# imu_node.net
KiCad netlist of a schematic drawn in EAGLE
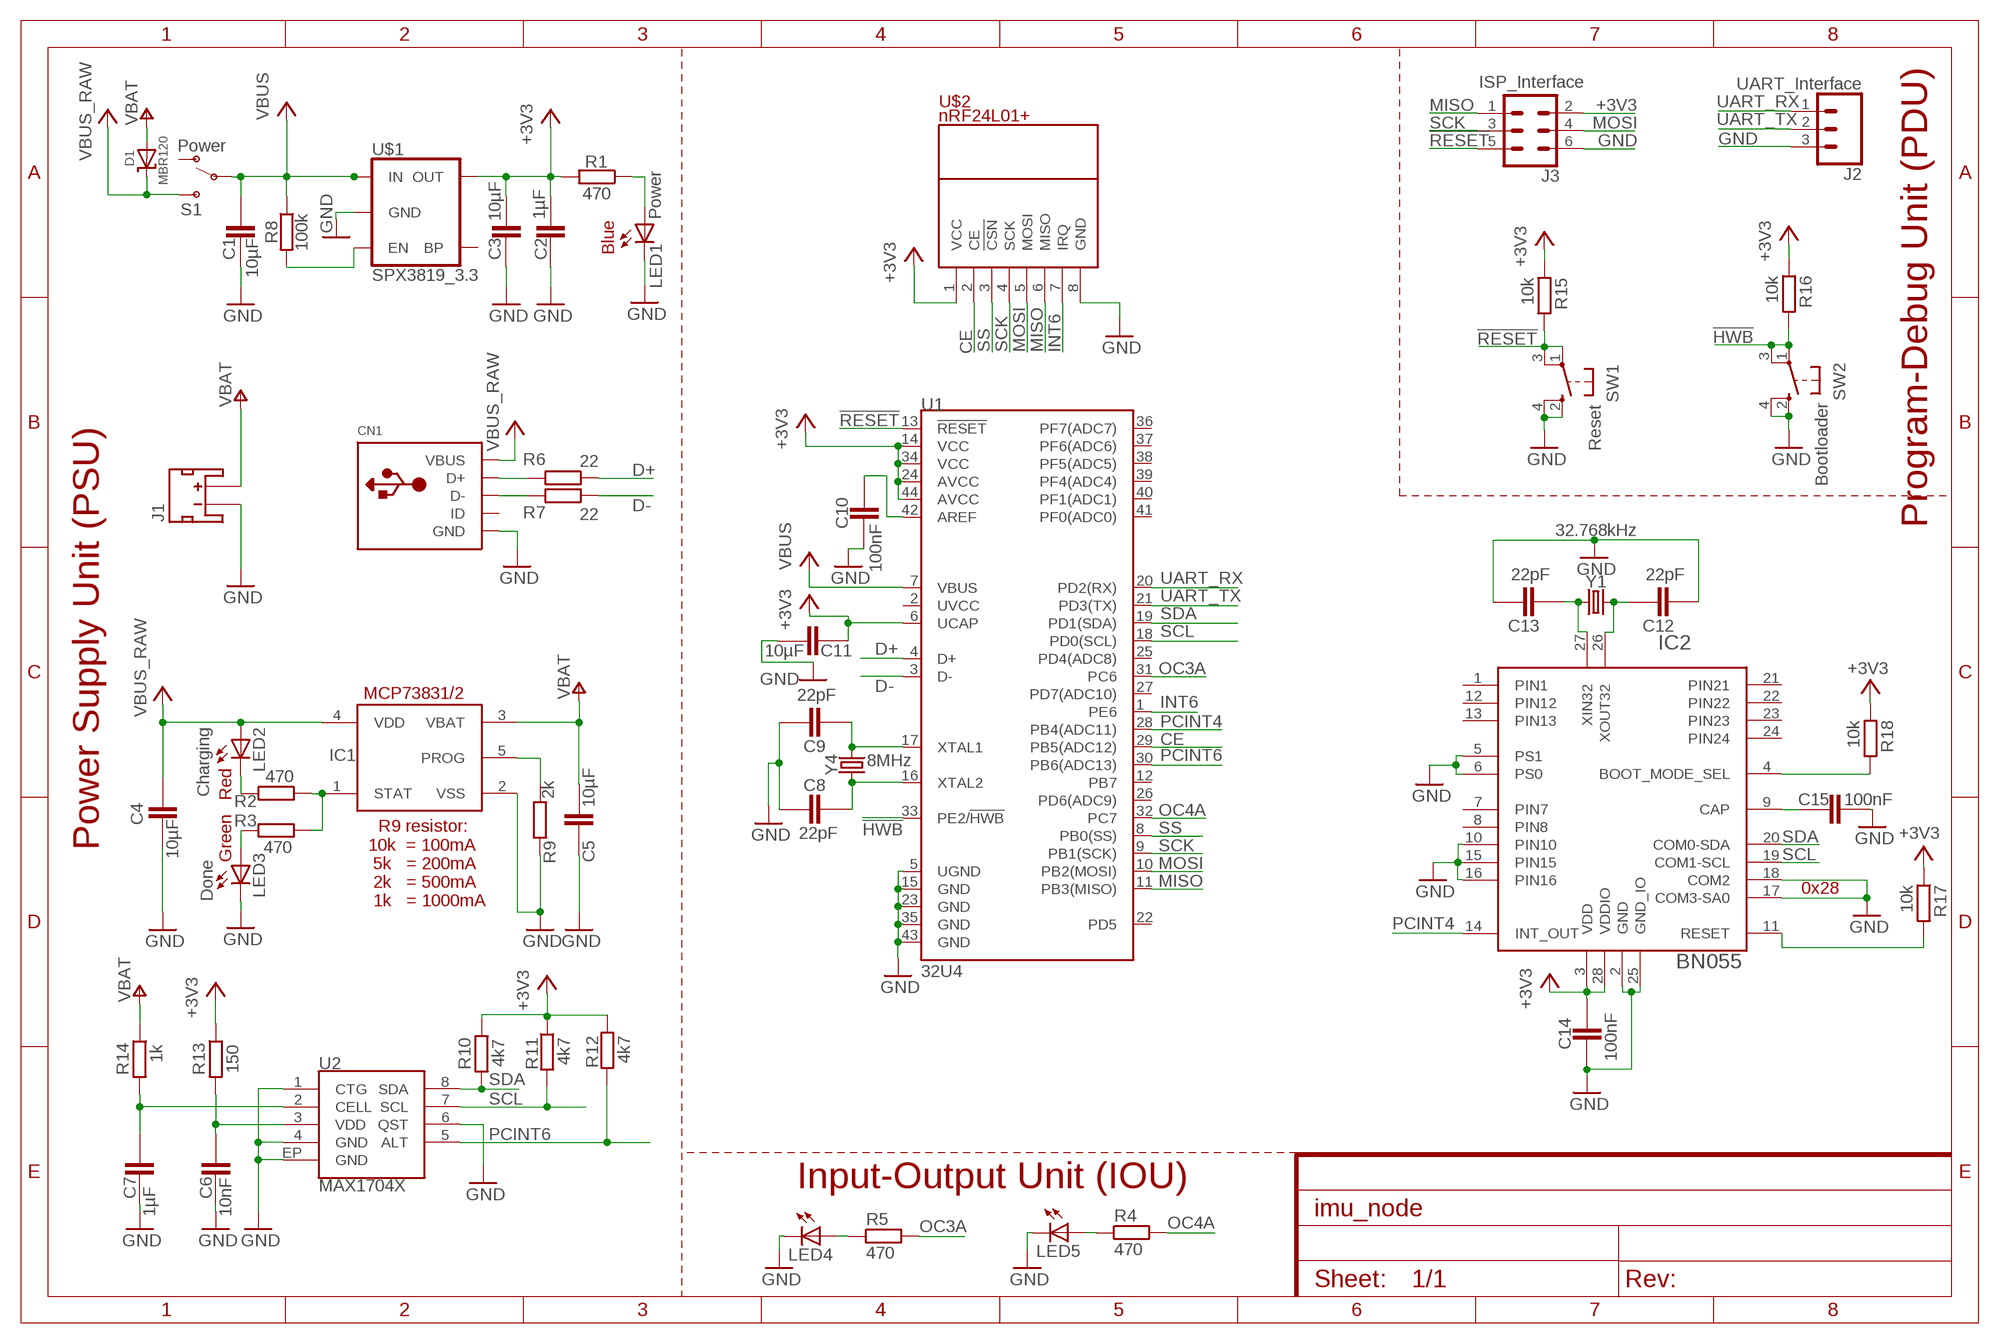
[diagram p0: schematic, sheet 1]

(export (version "E")
  (design (tool "Eeschema 10.0.6"))
  (components
    (comp (ref "C1")
      (value "10µF")
      (footprint "eagle-import:CAPC1608X92N")
      (libsource (lib "eagle-import") (part "CAPACITOR_0603"))
    )
    (comp (ref "C2")
      (value "1µF")
      (footprint "eagle-import:CAPC1608X92N")
      (libsource (lib "eagle-import") (part "CAPACITOR_0603"))
    )
    (comp (ref "C3")
      (value "10µF")
      (footprint "eagle-import:CAPC1608X92N")
      (libsource (lib "eagle-import") (part "CAPACITOR_0603"))
    )
    (comp (ref "C4")
      (value "10µF")
      (footprint "eagle-import:CAPC1608X92N")
      (libsource (lib "eagle-import") (part "CAPACITOR_0603"))
    )
    (comp (ref "C5")
      (value "10µF")
      (footprint "eagle-import:CAPC1608X92N")
      (libsource (lib "eagle-import") (part "CAPACITOR_0603"))
    )
    (comp (ref "C6")
      (value "10nF")
      (footprint "eagle-import:CAPC1608X92N")
      (libsource (lib "eagle-import") (part "CAPACITOR_0603"))
    )
    (comp (ref "C7")
      (value "1µF")
      (footprint "eagle-import:CAPC1608X92N")
      (libsource (lib "eagle-import") (part "CAPACITOR_0603"))
    )
    (comp (ref "C8")
      (value "22pF")
      (footprint "eagle-import:CAPC1608X92N")
      (libsource (lib "eagle-import") (part "CAPACITOR_0603"))
    )
    (comp (ref "C9")
      (value "22pF")
      (footprint "eagle-import:CAPC1608X92N")
      (libsource (lib "eagle-import") (part "CAPACITOR_0603"))
    )
    (comp (ref "C10")
      (value "100nF")
      (footprint "eagle-import:CAPC1608X92N")
      (libsource (lib "eagle-import") (part "CAPACITOR_0603"))
    )
    (comp (ref "C11")
      (value "10µF")
      (footprint "eagle-import:CAPC1608X92N")
      (libsource (lib "eagle-import") (part "CAPACITOR_0603"))
    )
    (comp (ref "C12")
      (value "22pF")
      (footprint "eagle-import:CAPC1608X92N")
      (libsource (lib "eagle-import") (part "CAPACITOR_0603"))
    )
    (comp (ref "C13")
      (value "22pF")
      (footprint "eagle-import:CAPC1608X92N")
      (libsource (lib "eagle-import") (part "CAPACITOR_0603"))
    )
    (comp (ref "C14")
      (value "100nF")
      (footprint "eagle-import:CAPC1608X92N")
      (libsource (lib "eagle-import") (part "CAPACITOR_0603"))
    )
    (comp (ref "C15")
      (value "100nF")
      (footprint "eagle-import:CAPC1608X92N")
      (libsource (lib "eagle-import") (part "CAPACITOR_0603"))
    )
    (comp (ref "CN1")
      (value "USBMINIB")
      (footprint "eagle-import:USB-MINIB")
      (libsource (lib "eagle-import") (part "USBMINIB"))
    )
    (comp (ref "D1")
      (value "MBR120")
      (footprint "eagle-import:SOD-123FL")
      (libsource (lib "eagle-import") (part "DIODE_SOD-123FL"))
    )
    (comp (ref "IC1")
      (value "MCP73831/OT")
      (footprint "eagle-import:SOT23-5L")
      (libsource (lib "eagle-import") (part "MCP73831/OT"))
    )
    (comp (ref "IC2")
      (value "BN055")
      (footprint "eagle-import:LGA-28_3.80X5.20_0.5")
      (fields (field (name "PART_NUMBER") "BNO055"))
      (libsource (lib "eagle-import") (part "1658_BNO055"))
    )
    (comp (ref "J1")
      (value "LiPo Battery")
      (footprint "eagle-import:JST-2-SMD")
      (libsource (lib "eagle-import") (part "JST_2MM_MALE"))
    )
    (comp (ref "J2")
      (value "UART_Interface")
      (footprint "eagle-import:1X03")
      (libsource (lib "eagle-import") (part "CONN_03"))
    )
    (comp (ref "J3")
      (value "ISP_Interface")
      (footprint "eagle-import:2X3")
      (libsource (lib "eagle-import") (part "CONN_03X2FEMALE"))
    )
    (comp (ref "LED1")
      (value "Power")
      (footprint "eagle-import:CHIPLED_0603")
      (libsource (lib "eagle-import") (part "LEDCHIPLED_0603"))
    )
    (comp (ref "LED2")
      (value "Charging")
      (footprint "eagle-import:CHIPLED_0603")
      (libsource (lib "eagle-import") (part "LEDCHIPLED_0603"))
    )
    (comp (ref "LED3")
      (value "Done")
      (footprint "eagle-import:CHIPLED_0603")
      (libsource (lib "eagle-import") (part "LEDCHIPLED_0603"))
    )
    (comp (ref "LED4")
      (value "LEDCHIPLED_0603")
      (footprint "eagle-import:CHIPLED_0603")
      (libsource (lib "eagle-import") (part "LEDCHIPLED_0603"))
    )
    (comp (ref "LED5")
      (value "LEDCHIPLED_0603")
      (footprint "eagle-import:CHIPLED_0603")
      (libsource (lib "eagle-import") (part "LEDCHIPLED_0603"))
    )
    (comp (ref "R1")
      (value "470")
      (footprint "eagle-import:RESC1608X55N")
      (libsource (lib "eagle-import") (part "RESISTOR_0603"))
    )
    (comp (ref "R2")
      (value "470")
      (footprint "eagle-import:RESC1608X55N")
      (libsource (lib "eagle-import") (part "RESISTOR_0603"))
    )
    (comp (ref "R3")
      (value "470")
      (footprint "eagle-import:RESC1608X55N")
      (libsource (lib "eagle-import") (part "RESISTOR_0603"))
    )
    (comp (ref "R4")
      (value "470")
      (footprint "eagle-import:RESC1608X55N")
      (libsource (lib "eagle-import") (part "RESISTOR_0603"))
    )
    (comp (ref "R5")
      (value "470")
      (footprint "eagle-import:RESC1608X55N")
      (libsource (lib "eagle-import") (part "RESISTOR_0603"))
    )
    (comp (ref "R6")
      (value "22")
      (footprint "eagle-import:RESC1608X55N")
      (libsource (lib "eagle-import") (part "RESISTOR_0603"))
    )
    (comp (ref "R7")
      (value "22")
      (footprint "eagle-import:RESC1608X55N")
      (libsource (lib "eagle-import") (part "RESISTOR_0603"))
    )
    (comp (ref "R8")
      (value "100k")
      (footprint "eagle-import:RESC1608X55N")
      (libsource (lib "eagle-import") (part "RESISTOR_0603"))
    )
    (comp (ref "R9")
      (value "2k")
      (footprint "eagle-import:RESC1608X55N")
      (libsource (lib "eagle-import") (part "RESISTOR_0603"))
    )
    (comp (ref "R10")
      (value "4k7")
      (footprint "eagle-import:RESC1608X55N")
      (libsource (lib "eagle-import") (part "RESISTOR_0603"))
    )
    (comp (ref "R11")
      (value "4k7")
      (footprint "eagle-import:RESC1608X55N")
      (libsource (lib "eagle-import") (part "RESISTOR_0603"))
    )
    (comp (ref "R12")
      (value "4k7")
      (footprint "eagle-import:RESC1608X55N")
      (libsource (lib "eagle-import") (part "RESISTOR_0603"))
    )
    (comp (ref "R13")
      (value "150")
      (footprint "eagle-import:RESC1608X55N")
      (libsource (lib "eagle-import") (part "RESISTOR_0603"))
    )
    (comp (ref "R14")
      (value "1k")
      (footprint "eagle-import:RESC1608X55N")
      (libsource (lib "eagle-import") (part "RESISTOR_0603"))
    )
    (comp (ref "R15")
      (value "10k")
      (footprint "eagle-import:RESC1608X55N")
      (libsource (lib "eagle-import") (part "RESISTOR_0603"))
    )
    (comp (ref "R16")
      (value "10k")
      (footprint "eagle-import:RESC1608X55N")
      (libsource (lib "eagle-import") (part "RESISTOR_0603"))
    )
    (comp (ref "R17")
      (value "10k")
      (footprint "eagle-import:RESC1608X55N")
      (libsource (lib "eagle-import") (part "RESISTOR_0603"))
    )
    (comp (ref "R18")
      (value "10k")
      (footprint "eagle-import:RESC1608X55N")
      (libsource (lib "eagle-import") (part "RESISTOR_0603"))
    )
    (comp (ref "S1")
      (value "Power")
      (footprint "eagle-import:SWITCH_SPST_SMD_A")
      (libsource (lib "eagle-import") (part "SWITCH-SPDT-SMD-RIGHT-ANGLE"))
    )
    (comp (ref "SW1")
      (value "Reset")
      (footprint "eagle-import:KMR2")
      (libsource (lib "eagle-import") (part "SPST_TACT-KMR2"))
    )
    (comp (ref "SW2")
      (value "Bootloader")
      (footprint "eagle-import:KMR2")
      (libsource (lib "eagle-import") (part "SPST_TACT-KMR2"))
    )
    (comp (ref "U$1")
      (value "SPX3819_3.3")
      (footprint "eagle-import:SOT23-5")
      (libsource (lib "eagle-import") (part "V_REG_SPX3819-SOT23-5"))
    )
    (comp (ref "U$2")
      (value "nRF24L01+")
      (footprint "eagle-import:6-PIN-BREAKOUT")
      (libsource (lib "eagle-import") (part "6-PIN-BREAKOUT6-PIN-BREAKOUT"))
    )
    (comp (ref "U1")
      (value "32U4")
      (footprint "eagle-import:TQFP44")
      (libsource (lib "eagle-import") (part "ATMEGA32U4TQFP-44"))
    )
    (comp (ref "U2")
      (value "MAX1704X")
      (footprint "eagle-import:TDFN-8")
      (libsource (lib "eagle-import") (part "MAX1704X"))
    )
    (comp (ref "Y1")
      (value "32.768kHz")
      (footprint "eagle-import:CRYSTAL-SMD-3.2X1.5MM")
      (libsource (lib "eagle-import") (part "CRYSTAL-32.768KHZSMD-3.2X1.5"))
    )
    (comp (ref "Y4")
      (value "8MHz")
      (footprint "eagle-import:CRYSTAL-SMD-5X3.2-4PAD")
      (libsource (lib "eagle-import") (part "CRYSTAL-8MHZSMD-5X3.2"))
    )
  )
  (nets
    (net (code "1") (name "+3V3") (class "Default")
      (node (ref "C11") (pin "1") (pinfunction "1_1") (pintype "passive"))
      (node (ref "C14") (pin "1") (pinfunction "1_1") (pintype "passive"))
      (node (ref "C2") (pin "2") (pinfunction "2_2") (pintype "passive"))
      (node (ref "C3") (pin "2") (pinfunction "2_2") (pintype "passive"))
      (node (ref "IC2") (pin "28") (pinfunction "VDDIO_28") (pintype "power_in"))
      (node (ref "IC2") (pin "3") (pinfunction "VDD_3") (pintype "power_in"))
      (node (ref "J3") (pin "2") (pinfunction "2_2") (pintype "bidirectional"))
      (node (ref "R1") (pin "2") (pinfunction "2_2") (pintype "passive"))
      (node (ref "R10") (pin "1") (pinfunction "1_1") (pintype "passive"))
      (node (ref "R11") (pin "1") (pinfunction "1_1") (pintype "passive"))
      (node (ref "R12") (pin "1") (pinfunction "1_1") (pintype "passive"))
      (node (ref "R13") (pin "1") (pinfunction "1_1") (pintype "passive"))
      (node (ref "R15") (pin "1") (pinfunction "1_1") (pintype "passive"))
      (node (ref "R16") (pin "1") (pinfunction "1_1") (pintype "passive"))
      (node (ref "R17") (pin "1") (pinfunction "1_1") (pintype "passive"))
      (node (ref "R18") (pin "1") (pinfunction "1_1") (pintype "passive"))
      (node (ref "U$1") (pin "5") (pinfunction "OUT_5") (pintype "passive"))
      (node (ref "U$2") (pin "1") (pinfunction "VCC_1") (pintype "bidirectional"))
      (node (ref "U1") (pin "14") (pinfunction "VCC_14") (pintype "bidirectional"))
      (node (ref "U1") (pin "24") (pinfunction "AVCC_24") (pintype "bidirectional"))
      (node (ref "U1") (pin "34") (pinfunction "VCC_34") (pintype "bidirectional"))
      (node (ref "U1") (pin "44") (pinfunction "AVCC_44") (pintype "bidirectional"))
      (node (ref "U1") (pin "6") (pinfunction "UCAP_6") (pintype "bidirectional"))
    )
    (net (code "2") (name "/CE") (class "Default")
      (node (ref "U$2") (pin "2") (pinfunction "CE_2") (pintype "bidirectional"))
      (node (ref "U1") (pin "29") (pinfunction "PB5(ADC12)_29") (pintype "bidirectional"))
    )
    (net (code "3") (name "/D+") (class "Default")
      (node (ref "R6") (pin "1") (pinfunction "1_1") (pintype "passive"))
      (node (ref "U1") (pin "4") (pinfunction "D+_4") (pintype "bidirectional"))
    )
    (net (code "4") (name "/D-") (class "Default")
      (node (ref "R7") (pin "1") (pinfunction "1_1") (pintype "passive"))
      (node (ref "U1") (pin "3") (pinfunction "D-_3") (pintype "bidirectional"))
    )
    (net (code "5") (name "/INT6") (class "Default")
      (node (ref "U$2") (pin "7") (pinfunction "IRQ_7") (pintype "bidirectional"))
      (node (ref "U1") (pin "1") (pinfunction "PE6_1") (pintype "bidirectional"))
    )
    (net (code "6") (name "/MISO") (class "Default")
      (node (ref "J3") (pin "1") (pinfunction "1_1") (pintype "bidirectional"))
      (node (ref "U$2") (pin "6") (pinfunction "MISO_6") (pintype "bidirectional"))
      (node (ref "U1") (pin "11") (pinfunction "PB3(MISO)_11") (pintype "bidirectional"))
    )
    (net (code "7") (name "/MOSI") (class "Default")
      (node (ref "J3") (pin "4") (pinfunction "4_4") (pintype "bidirectional"))
      (node (ref "U$2") (pin "5") (pinfunction "MOSI_5") (pintype "bidirectional"))
      (node (ref "U1") (pin "10") (pinfunction "PB2(MOSI)_10") (pintype "bidirectional"))
    )
    (net (code "8") (name "/OC3A") (class "Default")
      (node (ref "R5") (pin "2") (pinfunction "2_2") (pintype "passive"))
      (node (ref "U1") (pin "31") (pinfunction "PC6_31") (pintype "bidirectional"))
    )
    (net (code "9") (name "/OC4A") (class "Default")
      (node (ref "R4") (pin "2") (pinfunction "2_2") (pintype "passive"))
      (node (ref "U1") (pin "32") (pinfunction "PC7_32") (pintype "bidirectional"))
    )
    (net (code "10") (name "/PCINT4") (class "Default")
      (node (ref "IC2") (pin "14") (pinfunction "INT_OUT_14") (pintype "output"))
      (node (ref "U1") (pin "28") (pinfunction "PB4(ADC11)_28") (pintype "bidirectional"))
    )
    (net (code "11") (name "/PCINT6") (class "Default")
      (node (ref "R12") (pin "2") (pinfunction "2_2") (pintype "passive"))
      (node (ref "U1") (pin "30") (pinfunction "PB6(ADC13)_30") (pintype "bidirectional"))
      (node (ref "U2") (pin "5") (pinfunction "ALT_5") (pintype "bidirectional"))
    )
    (net (code "12") (name "/SCK") (class "Default")
      (node (ref "J3") (pin "3") (pinfunction "3_3") (pintype "bidirectional"))
      (node (ref "U$2") (pin "4") (pinfunction "SCK_4") (pintype "bidirectional"))
      (node (ref "U1") (pin "9") (pinfunction "PB1(SCK)_9") (pintype "bidirectional"))
    )
    (net (code "13") (name "/SCL") (class "Default")
      (node (ref "IC2") (pin "19") (pinfunction "COM1-SCL_19") (pintype "bidirectional"))
      (node (ref "R11") (pin "2") (pinfunction "2_2") (pintype "passive"))
      (node (ref "U1") (pin "18") (pinfunction "PD0(SCL)_18") (pintype "bidirectional"))
      (node (ref "U2") (pin "7") (pinfunction "SCL_7") (pintype "bidirectional"))
    )
    (net (code "14") (name "/SDA") (class "Default")
      (node (ref "IC2") (pin "20") (pinfunction "COM0-SDA_20") (pintype "bidirectional"))
      (node (ref "R10") (pin "2") (pinfunction "2_2") (pintype "passive"))
      (node (ref "U1") (pin "19") (pinfunction "PD1(SDA)_19") (pintype "bidirectional"))
      (node (ref "U2") (pin "8") (pinfunction "SDA_8") (pintype "bidirectional"))
    )
    (net (code "15") (name "/SS") (class "Default")
      (node (ref "U$2") (pin "3") (pinfunction "~{CSN}_3") (pintype "bidirectional"))
      (node (ref "U1") (pin "8") (pinfunction "PB0(SS)_8") (pintype "bidirectional"))
    )
    (net (code "16") (name "/UART_RX") (class "Default")
      (node (ref "J2") (pin "1") (pinfunction "1_1") (pintype "passive"))
      (node (ref "U1") (pin "20") (pinfunction "PD2(RX)_20") (pintype "bidirectional"))
    )
    (net (code "17") (name "/UART_TX") (class "Default")
      (node (ref "J2") (pin "2") (pinfunction "2_2") (pintype "passive"))
      (node (ref "U1") (pin "21") (pinfunction "PD3(TX)_21") (pintype "bidirectional"))
    )
    (net (code "18") (name "/~{HWB}") (class "Default")
      (node (ref "R16") (pin "2") (pinfunction "2_2") (pintype "passive"))
      (node (ref "SW2") (pin "1") (pinfunction "P_1") (pintype "passive"))
      (node (ref "SW2") (pin "3") (pinfunction "P1_3") (pintype "passive"))
      (node (ref "U1") (pin "33") (pinfunction "PE2/~{HWB}_33") (pintype "bidirectional"))
    )
    (net (code "19") (name "/~{RESET}") (class "Default")
      (node (ref "J3") (pin "5") (pinfunction "5_5") (pintype "bidirectional"))
      (node (ref "R15") (pin "2") (pinfunction "2_2") (pintype "passive"))
      (node (ref "SW1") (pin "1") (pinfunction "P_1") (pintype "passive"))
      (node (ref "SW1") (pin "3") (pinfunction "P1_3") (pintype "passive"))
      (node (ref "U1") (pin "13") (pinfunction "~{RESET}_13") (pintype "bidirectional"))
    )
    (net (code "20") (name "GND") (class "Default")
      (node (ref "C1") (pin "1") (pinfunction "1_1") (pintype "passive"))
      (node (ref "C10") (pin "2") (pinfunction "2_2") (pintype "passive"))
      (node (ref "C11") (pin "2") (pinfunction "2_2") (pintype "passive"))
      (node (ref "C12") (pin "1") (pinfunction "1_1") (pintype "passive"))
      (node (ref "C13") (pin "2") (pinfunction "2_2") (pintype "passive"))
      (node (ref "C14") (pin "2") (pinfunction "2_2") (pintype "passive"))
      (node (ref "C15") (pin "2") (pinfunction "2_2") (pintype "passive"))
      (node (ref "C2") (pin "1") (pinfunction "1_1") (pintype "passive"))
      (node (ref "C3") (pin "1") (pinfunction "1_1") (pintype "passive"))
      (node (ref "C4") (pin "1") (pinfunction "1_1") (pintype "passive"))
      (node (ref "C5") (pin "1") (pinfunction "1_1") (pintype "passive"))
      (node (ref "C6") (pin "1") (pinfunction "1_1") (pintype "passive"))
      (node (ref "C7") (pin "1") (pinfunction "1_1") (pintype "passive"))
      (node (ref "C8") (pin "2") (pinfunction "2_2") (pintype "passive"))
      (node (ref "C9") (pin "2") (pinfunction "2_2") (pintype "passive"))
      (node (ref "CN1") (pin "GND") (pinfunction "GND_GND") (pintype "power_in"))
      (node (ref "IC1") (pin "2") (pinfunction "VSS_2") (pintype "power_in"))
      (node (ref "IC2") (pin "10") (pinfunction "PIN10_10") (pintype "passive"))
      (node (ref "IC2") (pin "15") (pinfunction "PIN15_15") (pintype "passive"))
      (node (ref "IC2") (pin "16") (pinfunction "PIN16_16") (pintype "passive"))
      (node (ref "IC2") (pin "17") (pinfunction "COM3-SA0_17") (pintype "bidirectional"))
      (node (ref "IC2") (pin "18") (pinfunction "COM2_18") (pintype "bidirectional"))
      (node (ref "IC2") (pin "2") (pinfunction "GND_2") (pintype "power_in"))
      (node (ref "IC2") (pin "25") (pinfunction "GND_IO_25") (pintype "power_in"))
      (node (ref "IC2") (pin "5") (pinfunction "PS1_5") (pintype "input"))
      (node (ref "IC2") (pin "6") (pinfunction "PS0_6") (pintype "input"))
      (node (ref "J1") (pin "1") (pinfunction "-_1") (pintype "bidirectional"))
      (node (ref "J2") (pin "3") (pinfunction "3_3") (pintype "passive"))
      (node (ref "J3") (pin "6") (pinfunction "6_6") (pintype "bidirectional"))
      (node (ref "LED1") (pin "C") (pinfunction "C_C") (pintype "passive"))
      (node (ref "LED3") (pin "C") (pinfunction "C_C") (pintype "passive"))
      (node (ref "LED4") (pin "C") (pinfunction "C_C") (pintype "passive"))
      (node (ref "LED5") (pin "C") (pinfunction "C_C") (pintype "passive"))
      (node (ref "R9") (pin "2") (pinfunction "2_2") (pintype "passive"))
      (node (ref "SW1") (pin "2") (pinfunction "S_2") (pintype "passive"))
      (node (ref "SW1") (pin "4") (pinfunction "S1_4") (pintype "passive"))
      (node (ref "SW2") (pin "2") (pinfunction "S_2") (pintype "passive"))
      (node (ref "SW2") (pin "4") (pinfunction "S1_4") (pintype "passive"))
      (node (ref "U$1") (pin "2") (pinfunction "GND_2") (pintype "input"))
      (node (ref "U$2") (pin "8") (pinfunction "GND_8") (pintype "bidirectional"))
      (node (ref "U1") (pin "15") (pinfunction "GND_15") (pintype "bidirectional"))
      (node (ref "U1") (pin "23") (pinfunction "GND_23") (pintype "bidirectional"))
      (node (ref "U1") (pin "35") (pinfunction "GND_35") (pintype "bidirectional"))
      (node (ref "U1") (pin "43") (pinfunction "GND_43") (pintype "bidirectional"))
      (node (ref "U1") (pin "5") (pinfunction "UGND_5") (pintype "bidirectional"))
      (node (ref "U2") (pin "1") (pinfunction "CTG_1") (pintype "bidirectional"))
      (node (ref "U2") (pin "4") (pinfunction "GND_4") (pintype "bidirectional"))
      (node (ref "U2") (pin "6") (pinfunction "QST_6") (pintype "bidirectional"))
      (node (ref "U2") (pin "EP") (pinfunction "GND_EP") (pintype "bidirectional"))
    )
    (net (code "21") (name "Net-(CN1-PadD+)") (class "Default")
      (node (ref "CN1") (pin "D+") (pinfunction "D+_D+") (pintype "bidirectional"))
      (node (ref "R6") (pin "2") (pinfunction "2_2") (pintype "passive"))
    )
    (net (code "22") (name "Net-(CN1-PadD-)") (class "Default")
      (node (ref "CN1") (pin "D-") (pinfunction "D-_D-") (pintype "bidirectional"))
      (node (ref "R7") (pin "2") (pinfunction "2_2") (pintype "passive"))
    )
    (net (code "23") (name "Net-(IC1-PROG)") (class "Default")
      (node (ref "IC1") (pin "5") (pinfunction "PROG_5") (pintype "input"))
      (node (ref "R9") (pin "1") (pinfunction "1_1") (pintype "passive"))
    )
    (net (code "24") (name "Net-(IC1-STAT)") (class "Default")
      (node (ref "IC1") (pin "1") (pinfunction "STAT_1") (pintype "output"))
      (node (ref "R2") (pin "1") (pinfunction "1_1") (pintype "passive"))
      (node (ref "R3") (pin "1") (pinfunction "1_1") (pintype "passive"))
    )
    (net (code "25") (name "Net-(IC2-BOOT_MODE_SEL)") (class "Default")
      (node (ref "IC2") (pin "4") (pinfunction "BOOT_MODE_SEL_4") (pintype "input"))
      (node (ref "R18") (pin "2") (pinfunction "2_2") (pintype "passive"))
    )
    (net (code "26") (name "Net-(IC2-CAP)") (class "Default")
      (node (ref "C15") (pin "1") (pinfunction "1_1") (pintype "passive"))
      (node (ref "IC2") (pin "9") (pinfunction "CAP_9") (pintype "tri_state"))
    )
    (net (code "27") (name "Net-(IC2-RESET)") (class "Default")
      (node (ref "IC2") (pin "11") (pinfunction "RESET_11") (pintype "input"))
      (node (ref "R17") (pin "2") (pinfunction "2_2") (pintype "passive"))
    )
    (net (code "28") (name "Net-(IC2-XIN32)") (class "Default")
      (node (ref "C13") (pin "1") (pinfunction "1_1") (pintype "passive"))
      (node (ref "IC2") (pin "27") (pinfunction "XIN32_27") (pintype "bidirectional"))
      (node (ref "Y1") (pin "P$1") (pinfunction "1_P$1") (pintype "passive"))
    )
    (net (code "29") (name "Net-(IC2-XOUT32)") (class "Default")
      (node (ref "C12") (pin "2") (pinfunction "2_2") (pintype "passive"))
      (node (ref "IC2") (pin "26") (pinfunction "XOUT32_26") (pintype "output"))
      (node (ref "Y1") (pin "P$2") (pinfunction "2_P$2") (pintype "passive"))
    )
    (net (code "30") (name "Net-(LED1-PadA)") (class "Default")
      (node (ref "LED1") (pin "A") (pinfunction "A_A") (pintype "passive"))
      (node (ref "R1") (pin "1") (pinfunction "1_1") (pintype "passive"))
    )
    (net (code "31") (name "Net-(LED2-PadC)") (class "Default")
      (node (ref "LED2") (pin "C") (pinfunction "C_C") (pintype "passive"))
      (node (ref "R2") (pin "2") (pinfunction "2_2") (pintype "passive"))
    )
    (net (code "32") (name "Net-(LED3-PadA)") (class "Default")
      (node (ref "LED3") (pin "A") (pinfunction "A_A") (pintype "passive"))
      (node (ref "R3") (pin "2") (pinfunction "2_2") (pintype "passive"))
    )
    (net (code "33") (name "Net-(LED4-PadA)") (class "Default")
      (node (ref "LED4") (pin "A") (pinfunction "A_A") (pintype "passive"))
      (node (ref "R5") (pin "1") (pinfunction "1_1") (pintype "passive"))
    )
    (net (code "34") (name "Net-(LED5-PadA)") (class "Default")
      (node (ref "LED5") (pin "A") (pinfunction "A_A") (pintype "passive"))
      (node (ref "R4") (pin "1") (pinfunction "1_1") (pintype "passive"))
    )
    (net (code "35") (name "Net-(U$1-EN)") (class "Default")
      (node (ref "R8") (pin "2") (pinfunction "2_2") (pintype "passive"))
      (node (ref "U$1") (pin "3") (pinfunction "EN_3") (pintype "input"))
    )
    (net (code "36") (name "Net-(U1-AREF)") (class "Default")
      (node (ref "C10") (pin "1") (pinfunction "1_1") (pintype "passive"))
      (node (ref "U1") (pin "42") (pinfunction "AREF_42") (pintype "bidirectional"))
    )
    (net (code "37") (name "Net-(U1-XTAL1)") (class "Default")
      (node (ref "C9") (pin "1") (pinfunction "1_1") (pintype "passive"))
      (node (ref "U1") (pin "17") (pinfunction "XTAL1_17") (pintype "bidirectional"))
      (node (ref "Y4") (pin "3") (pinfunction "2_3") (pintype "passive"))
    )
    (net (code "38") (name "Net-(U1-XTAL2)") (class "Default")
      (node (ref "C8") (pin "1") (pinfunction "1_1") (pintype "passive"))
      (node (ref "U1") (pin "16") (pinfunction "XTAL2_16") (pintype "bidirectional"))
      (node (ref "Y4") (pin "1") (pinfunction "1_1") (pintype "passive"))
    )
    (net (code "39") (name "Net-(U2-CELL)") (class "Default")
      (node (ref "C7") (pin "2") (pinfunction "2_2") (pintype "passive"))
      (node (ref "R14") (pin "2") (pinfunction "2_2") (pintype "passive"))
      (node (ref "U2") (pin "2") (pinfunction "CELL_2") (pintype "bidirectional"))
    )
    (net (code "40") (name "Net-(U2-VDD)") (class "Default")
      (node (ref "C6") (pin "2") (pinfunction "2_2") (pintype "passive"))
      (node (ref "R13") (pin "2") (pinfunction "2_2") (pintype "passive"))
      (node (ref "U2") (pin "3") (pinfunction "VDD_3") (pintype "bidirectional"))
    )
    (net (code "41") (name "VBAT") (class "Default")
      (node (ref "C5") (pin "2") (pinfunction "2_2") (pintype "passive"))
      (node (ref "D1") (pin "A") (pinfunction "A_A") (pintype "passive"))
      (node (ref "IC1") (pin "3") (pinfunction "VBAT_3") (pintype "bidirectional"))
      (node (ref "J1") (pin "2") (pinfunction "+_2") (pintype "bidirectional"))
      (node (ref "R14") (pin "1") (pinfunction "1_1") (pintype "passive"))
    )
    (net (code "42") (name "VBUS") (class "Default")
      (node (ref "C1") (pin "2") (pinfunction "2_2") (pintype "passive"))
      (node (ref "R8") (pin "1") (pinfunction "1_1") (pintype "passive"))
      (node (ref "S1") (pin "2") (pinfunction "P_2") (pintype "passive"))
      (node (ref "U$1") (pin "1") (pinfunction "IN_1") (pintype "input"))
      (node (ref "U1") (pin "7") (pinfunction "VBUS_7") (pintype "bidirectional"))
    )
    (net (code "43") (name "VBUS_RAW") (class "Default")
      (node (ref "C4") (pin "2") (pinfunction "2_2") (pintype "passive"))
      (node (ref "CN1") (pin "VBUS") (pinfunction "VBUS_VBUS") (pintype "power_in"))
      (node (ref "D1") (pin "C") (pinfunction "C_C") (pintype "passive"))
      (node (ref "IC1") (pin "4") (pinfunction "VDD_4") (pintype "power_in"))
      (node (ref "LED2") (pin "A") (pinfunction "A_A") (pintype "passive"))
      (node (ref "S1") (pin "3") (pinfunction "S_3") (pintype "passive"))
    )
    (net (code "44") (name "unconnected-(CN1-PadID)") (class "Default")
      (node (ref "CN1") (pin "ID") (pinfunction "ID_ID") (pintype "bidirectional"))
    )
    (net (code "45") (name "unconnected-(IC2-PIN1-Pad1)") (class "Default")
      (node (ref "IC2") (pin "1") (pinfunction "PIN1_1") (pintype "no_connect"))
    )
    (net (code "46") (name "unconnected-(IC2-PIN7-Pad7)") (class "Default")
      (node (ref "IC2") (pin "7") (pinfunction "PIN7_7") (pintype "tri_state"))
    )
    (net (code "47") (name "unconnected-(IC2-PIN8-Pad8)") (class "Default")
      (node (ref "IC2") (pin "8") (pinfunction "PIN8_8") (pintype "tri_state"))
    )
    (net (code "48") (name "unconnected-(IC2-PIN12-Pad12)") (class "Default")
      (node (ref "IC2") (pin "12") (pinfunction "PIN12_12") (pintype "passive"))
    )
    (net (code "49") (name "unconnected-(IC2-PIN13-Pad13)") (class "Default")
      (node (ref "IC2") (pin "13") (pinfunction "PIN13_13") (pintype "passive"))
    )
    (net (code "50") (name "unconnected-(IC2-PIN21-Pad21)") (class "Default")
      (node (ref "IC2") (pin "21") (pinfunction "PIN21_21") (pintype "passive"))
    )
    (net (code "51") (name "unconnected-(IC2-PIN22-Pad22)") (class "Default")
      (node (ref "IC2") (pin "22") (pinfunction "PIN22_22") (pintype "passive"))
    )
    (net (code "52") (name "unconnected-(IC2-PIN23-Pad23)") (class "Default")
      (node (ref "IC2") (pin "23") (pinfunction "PIN23_23") (pintype "passive"))
    )
    (net (code "53") (name "unconnected-(IC2-PIN24-Pad24)") (class "Default")
      (node (ref "IC2") (pin "24") (pinfunction "PIN24_24") (pintype "passive"))
    )
    (net (code "54") (name "unconnected-(J1-PAD1-PadNC1)") (class "Default")
      (node (ref "J1") (pin "NC1") (pinfunction "PAD1_NC1") (pintype "bidirectional"))
    )
    (net (code "55") (name "unconnected-(J1-PAD2-PadNC2)") (class "Default")
      (node (ref "J1") (pin "NC2") (pinfunction "PAD2_NC2") (pintype "bidirectional"))
    )
    (net (code "56") (name "unconnected-(S1-O-Pad1)") (class "Default")
      (node (ref "S1") (pin "1") (pinfunction "O_1") (pintype "passive"))
    )
    (net (code "57") (name "unconnected-(U$1-BP-Pad4)") (class "Default")
      (node (ref "U$1") (pin "4") (pinfunction "BP_4") (pintype "input"))
    )
    (net (code "58") (name "unconnected-(U1-PB7-Pad12)") (class "Default")
      (node (ref "U1") (pin "12") (pinfunction "PB7_12") (pintype "bidirectional"))
    )
    (net (code "59") (name "unconnected-(U1-PD4(ADC8)-Pad25)") (class "Default")
      (node (ref "U1") (pin "25") (pinfunction "PD4(ADC8)_25") (pintype "bidirectional"))
    )
    (net (code "60") (name "unconnected-(U1-PD5-Pad22)") (class "Default")
      (node (ref "U1") (pin "22") (pinfunction "PD5_22") (pintype "bidirectional"))
    )
    (net (code "61") (name "unconnected-(U1-PD6(ADC9)-Pad26)") (class "Default")
      (node (ref "U1") (pin "26") (pinfunction "PD6(ADC9)_26") (pintype "bidirectional"))
    )
    (net (code "62") (name "unconnected-(U1-PD7(ADC10)-Pad27)") (class "Default")
      (node (ref "U1") (pin "27") (pinfunction "PD7(ADC10)_27") (pintype "bidirectional"))
    )
    (net (code "63") (name "unconnected-(U1-PF0(ADC0)-Pad41)") (class "Default")
      (node (ref "U1") (pin "41") (pinfunction "PF0(ADC0)_41") (pintype "bidirectional"))
    )
    (net (code "64") (name "unconnected-(U1-PF1(ADC1)-Pad40)") (class "Default")
      (node (ref "U1") (pin "40") (pinfunction "PF1(ADC1)_40") (pintype "bidirectional"))
    )
    (net (code "65") (name "unconnected-(U1-PF4(ADC4)-Pad39)") (class "Default")
      (node (ref "U1") (pin "39") (pinfunction "PF4(ADC4)_39") (pintype "bidirectional"))
    )
    (net (code "66") (name "unconnected-(U1-PF5(ADC5)-Pad38)") (class "Default")
      (node (ref "U1") (pin "38") (pinfunction "PF5(ADC5)_38") (pintype "bidirectional"))
    )
    (net (code "67") (name "unconnected-(U1-PF6(ADC6)-Pad37)") (class "Default")
      (node (ref "U1") (pin "37") (pinfunction "PF6(ADC6)_37") (pintype "bidirectional"))
    )
    (net (code "68") (name "unconnected-(U1-PF7(ADC7)-Pad36)") (class "Default")
      (node (ref "U1") (pin "36") (pinfunction "PF7(ADC7)_36") (pintype "bidirectional"))
    )
    (net (code "69") (name "unconnected-(U1-UVCC-Pad2)") (class "Default")
      (node (ref "U1") (pin "2") (pinfunction "UVCC_2") (pintype "bidirectional"))
    )
  )
)
